# Interface_Connector.net
KiCad netlist of a schematic drawn in Altium Designer
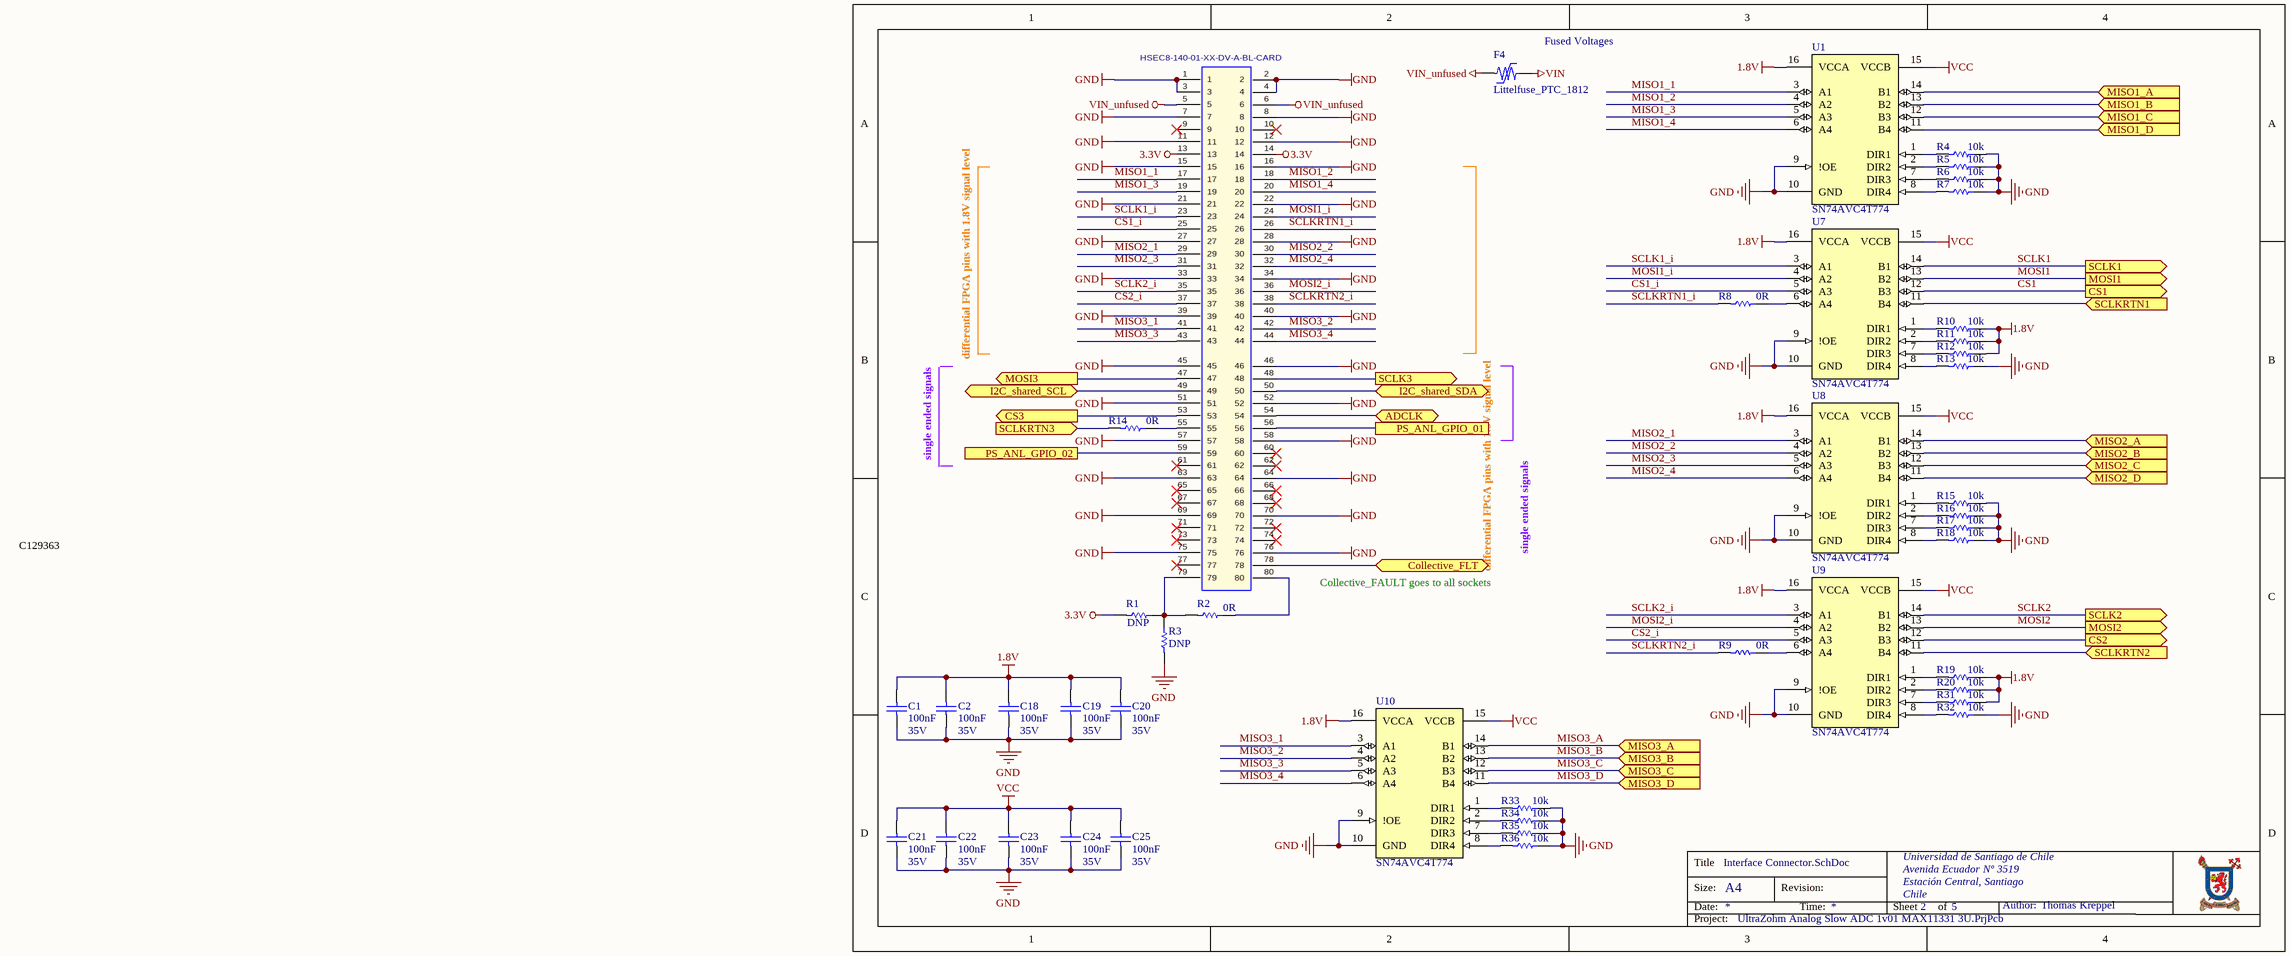
[diagram p0: Interface Connector.SchDoc]

(export (version "E")
  (design (tool "Eeschema 10.0.6"))
  (components
    (comp (ref "C1")
      (value "100nF")
      (footprint "CAP_0603")
      (description "Capacitor")
      (fields
        (field (name "MPN") "C0603C104M5RACTU")
        (field (name "MF") "KEMET")
        (field (name "VOLTAGE") "35V")
        (field (name "PUBLISHER") "Altium Limited")
      )
      (libsource (lib "Componentes_SOC") (part "Cap_0603"))
    )
    (comp (ref "C2")
      (value "100nF")
      (footprint "CAP_0603")
      (description "Capacitor")
      (fields
        (field (name "MPN") "C0603C104M5RACTU")
        (field (name "MF") "KEMET")
        (field (name "VOLTAGE") "35V")
        (field (name "PUBLISHER") "Altium Limited")
      )
      (libsource (lib "Componentes_SOC") (part "Cap_0603"))
    )
    (comp (ref "C18")
      (value "100nF")
      (footprint "CAP_0603")
      (description "Capacitor")
      (fields
        (field (name "MPN") "C0603C104M5RACTU")
        (field (name "MF") "KEMET")
        (field (name "VOLTAGE") "35V")
        (field (name "PUBLISHER") "Altium Limited")
      )
      (libsource (lib "Componentes_SOC") (part "Cap_0603"))
    )
    (comp (ref "C19")
      (value "100nF")
      (footprint "CAP_0603")
      (description "Capacitor")
      (fields
        (field (name "MPN") "C0603C104M5RACTU")
        (field (name "MF") "KEMET")
        (field (name "VOLTAGE") "35V")
        (field (name "PUBLISHER") "Altium Limited")
      )
      (libsource (lib "Componentes_SOC") (part "Cap_0603"))
    )
    (comp (ref "C20")
      (value "100nF")
      (footprint "CAP_0603")
      (description "Capacitor")
      (fields
        (field (name "MPN") "C0603C104M5RACTU")
        (field (name "MF") "KEMET")
        (field (name "VOLTAGE") "35V")
        (field (name "PUBLISHER") "Altium Limited")
      )
      (libsource (lib "Componentes_SOC") (part "Cap_0603"))
    )
    (comp (ref "C21")
      (value "100nF")
      (footprint "CAP_0603")
      (description "Capacitor")
      (fields
        (field (name "MPN") "C0603C104M5RACTU")
        (field (name "MF") "KEMET")
        (field (name "VOLTAGE") "35V")
        (field (name "PUBLISHER") "Altium Limited")
      )
      (libsource (lib "Componentes_SOC") (part "Cap_0603"))
    )
    (comp (ref "C22")
      (value "100nF")
      (footprint "CAP_0603")
      (description "Capacitor")
      (fields
        (field (name "MPN") "C0603C104M5RACTU")
        (field (name "MF") "KEMET")
        (field (name "VOLTAGE") "35V")
        (field (name "PUBLISHER") "Altium Limited")
      )
      (libsource (lib "Componentes_SOC") (part "Cap_0603"))
    )
    (comp (ref "C23")
      (value "100nF")
      (footprint "CAP_0603")
      (description "Capacitor")
      (fields
        (field (name "MPN") "C0603C104M5RACTU")
        (field (name "MF") "KEMET")
        (field (name "VOLTAGE") "35V")
        (field (name "PUBLISHER") "Altium Limited")
      )
      (libsource (lib "Componentes_SOC") (part "Cap_0603"))
    )
    (comp (ref "C24")
      (value "100nF")
      (footprint "CAP_0603")
      (description "Capacitor")
      (fields
        (field (name "MPN") "C0603C104M5RACTU")
        (field (name "MF") "KEMET")
        (field (name "VOLTAGE") "35V")
        (field (name "PUBLISHER") "Altium Limited")
      )
      (libsource (lib "Componentes_SOC") (part "Cap_0603"))
    )
    (comp (ref "C25")
      (value "100nF")
      (footprint "CAP_0603")
      (description "Capacitor")
      (fields
        (field (name "MPN") "C0603C104M5RACTU")
        (field (name "MF") "KEMET")
        (field (name "VOLTAGE") "35V")
        (field (name "PUBLISHER") "Altium Limited")
      )
      (libsource (lib "Componentes_SOC") (part "Cap_0603"))
    )
    (comp (ref "F4")
      (value "Littelfuse_PTC_1812")
      (footprint "1812_PTC_Polyfuse_Littelfuse")
      (description "POLYSWITCH RESETTABLE DEVICES")
      (fields
        (field (name "MPN") "miniASMDC110F/24")
        (field (name "MF") "Littelfuse")
        (field (name "CREATED") "2019_02_10_AGeiger")
        (field (name "CREATED FROM") "MHlatky")
      )
      (libsource (lib "user") (part "Littelfuse_PTC_1812"))
    )
    (comp (ref "R1")
      (value "DNP")
      (footprint "RES_0603")
      (fields
        (field (name "MPN") "CRCW06030000Z0EA")
        (field (name "TOLERANCE") "1%")
        (field (name "PUBLISHER") "Altium Limited")
      )
      (libsource (lib "Componentes_SOC") (part "Res0603"))
    )
    (comp (ref "R2")
      (value "0R")
      (footprint "RES_0603")
      (fields
        (field (name "MPN") "CRCW06030000Z0EA")
        (field (name "TOLERANCE") "1%")
        (field (name "PUBLISHER") "Altium Limited")
      )
      (libsource (lib "Componentes_SOC") (part "Res0603"))
    )
    (comp (ref "R3")
      (value "DNP")
      (footprint "RES_0603")
      (fields
        (field (name "MPN") "CRCW06030000Z0EA")
        (field (name "TOLERANCE") "1%")
        (field (name "PUBLISHER") "Altium Limited")
      )
      (libsource (lib "Componentes_SOC") (part "Res0603"))
    )
    (comp (ref "R4")
      (value "10k")
      (footprint "RES_0603")
      (fields (field (name "TOLERANCE") "1%") (field (name "PUBLISHER") "Altium Limited"))
      (libsource (lib "Componentes_SOC") (part "Res0603"))
    )
    (comp (ref "R5")
      (value "10k")
      (footprint "RES_0603")
      (fields (field (name "TOLERANCE") "1%") (field (name "PUBLISHER") "Altium Limited"))
      (libsource (lib "Componentes_SOC") (part "Res0603"))
    )
    (comp (ref "R6")
      (value "10k")
      (footprint "RES_0603")
      (fields (field (name "TOLERANCE") "1%") (field (name "PUBLISHER") "Altium Limited"))
      (libsource (lib "Componentes_SOC") (part "Res0603"))
    )
    (comp (ref "R7")
      (value "10k")
      (footprint "RES_0603")
      (fields (field (name "TOLERANCE") "1%") (field (name "PUBLISHER") "Altium Limited"))
      (libsource (lib "Componentes_SOC") (part "Res0603"))
    )
    (comp (ref "R8")
      (value "0R")
      (footprint "RES_0603")
      (fields (field (name "TOLERANCE") "1%") (field (name "PUBLISHER") "Altium Limited"))
      (libsource (lib "Componentes_SOC") (part "Res0603"))
    )
    (comp (ref "R9")
      (value "0R")
      (footprint "RES_0603")
      (fields (field (name "TOLERANCE") "1%") (field (name "PUBLISHER") "Altium Limited"))
      (libsource (lib "Componentes_SOC") (part "Res0603"))
    )
    (comp (ref "R10")
      (value "10k")
      (footprint "RES_0603")
      (fields (field (name "TOLERANCE") "1%") (field (name "PUBLISHER") "Altium Limited"))
      (libsource (lib "Componentes_SOC") (part "Res0603"))
    )
    (comp (ref "R11")
      (value "10k")
      (footprint "RES_0603")
      (fields (field (name "TOLERANCE") "1%") (field (name "PUBLISHER") "Altium Limited"))
      (libsource (lib "Componentes_SOC") (part "Res0603"))
    )
    (comp (ref "R12")
      (value "10k")
      (footprint "RES_0603")
      (fields (field (name "TOLERANCE") "1%") (field (name "PUBLISHER") "Altium Limited"))
      (libsource (lib "Componentes_SOC") (part "Res0603"))
    )
    (comp (ref "R13")
      (value "10k")
      (footprint "RES_0603")
      (fields (field (name "TOLERANCE") "1%") (field (name "PUBLISHER") "Altium Limited"))
      (libsource (lib "Componentes_SOC") (part "Res0603"))
    )
    (comp (ref "R14")
      (value "0R")
      (footprint "RES_0603")
      (fields (field (name "TOLERANCE") "1%") (field (name "PUBLISHER") "Altium Limited"))
      (libsource (lib "Componentes_SOC") (part "Res0603"))
    )
    (comp (ref "R15")
      (value "10k")
      (footprint "RES_0603")
      (fields (field (name "TOLERANCE") "1%") (field (name "PUBLISHER") "Altium Limited"))
      (libsource (lib "Componentes_SOC") (part "Res0603"))
    )
    (comp (ref "R16")
      (value "10k")
      (footprint "RES_0603")
      (fields (field (name "TOLERANCE") "1%") (field (name "PUBLISHER") "Altium Limited"))
      (libsource (lib "Componentes_SOC") (part "Res0603"))
    )
    (comp (ref "R17")
      (value "10k")
      (footprint "RES_0603")
      (fields (field (name "TOLERANCE") "1%") (field (name "PUBLISHER") "Altium Limited"))
      (libsource (lib "Componentes_SOC") (part "Res0603"))
    )
    (comp (ref "R18")
      (value "10k")
      (footprint "RES_0603")
      (fields (field (name "TOLERANCE") "1%") (field (name "PUBLISHER") "Altium Limited"))
      (libsource (lib "Componentes_SOC") (part "Res0603"))
    )
    (comp (ref "R19")
      (value "10k")
      (footprint "RES_0603")
      (fields (field (name "TOLERANCE") "1%") (field (name "PUBLISHER") "Altium Limited"))
      (libsource (lib "Componentes_SOC") (part "Res0603"))
    )
    (comp (ref "R20")
      (value "10k")
      (footprint "RES_0603")
      (fields (field (name "TOLERANCE") "1%") (field (name "PUBLISHER") "Altium Limited"))
      (libsource (lib "Componentes_SOC") (part "Res0603"))
    )
    (comp (ref "R31")
      (value "10k")
      (footprint "RES_0603")
      (fields (field (name "TOLERANCE") "1%") (field (name "PUBLISHER") "Altium Limited"))
      (libsource (lib "Componentes_SOC") (part "Res0603"))
    )
    (comp (ref "R32")
      (value "10k")
      (footprint "RES_0603")
      (fields (field (name "TOLERANCE") "1%") (field (name "PUBLISHER") "Altium Limited"))
      (libsource (lib "Componentes_SOC") (part "Res0603"))
    )
    (comp (ref "R33")
      (value "10k")
      (footprint "RES_0603")
      (fields (field (name "TOLERANCE") "1%") (field (name "PUBLISHER") "Altium Limited"))
      (libsource (lib "Componentes_SOC") (part "Res0603"))
    )
    (comp (ref "R34")
      (value "10k")
      (footprint "RES_0603")
      (fields (field (name "TOLERANCE") "1%") (field (name "PUBLISHER") "Altium Limited"))
      (libsource (lib "Componentes_SOC") (part "Res0603"))
    )
    (comp (ref "R35")
      (value "10k")
      (footprint "RES_0603")
      (fields (field (name "TOLERANCE") "1%") (field (name "PUBLISHER") "Altium Limited"))
      (libsource (lib "Componentes_SOC") (part "Res0603"))
    )
    (comp (ref "R36")
      (value "10k")
      (footprint "RES_0603")
      (fields (field (name "TOLERANCE") "1%") (field (name "PUBLISHER") "Altium Limited"))
      (libsource (lib "Componentes_SOC") (part "Res0603"))
    )
    (comp (ref "U1")
      (value "SN74AVC4T774")
      (footprint "TSOP65P640X120-16N")
      (fields
        (field (name "MF") "Texas Instruments")
        (field (name "MPN") "SN74AVC4T77PW")
        (field (name "LCSC PART NUMBER") "C129363")
        (field (name "CREATED") "2020_05_Kreppel")
      )
      (libsource (lib "Componentes_SOC") (part "SN74AVC4T774"))
    )
    (comp (ref "U7")
      (value "SN74AVC4T774")
      (footprint "TSOP65P640X120-16N")
      (fields
        (field (name "MF") "Texas Instruments")
        (field (name "MPN") "SN74AVC4T77PW")
        (field (name "LCSC PART NUMBER") "C129363")
        (field (name "CREATED") "2020_05_Kreppel")
      )
      (libsource (lib "Componentes_SOC") (part "SN74AVC4T774"))
    )
    (comp (ref "U8")
      (value "SN74AVC4T774")
      (footprint "TSOP65P640X120-16N")
      (fields
        (field (name "MF") "Texas Instruments")
        (field (name "MPN") "SN74AVC4T77PW")
        (field (name "LCSC PART NUMBER") "C129363")
        (field (name "CREATED") "2020_05_Kreppel")
      )
      (libsource (lib "Componentes_SOC") (part "SN74AVC4T774"))
    )
    (comp (ref "U9")
      (value "SN74AVC4T774")
      (footprint "TSOP65P640X120-16N")
      (fields
        (field (name "MF") "Texas Instruments")
        (field (name "MPN") "SN74AVC4T77PW")
        (field (name "LCSC PART NUMBER") "C129363")
        (field (name "CREATED") "2020_05_Kreppel")
      )
      (libsource (lib "Componentes_SOC") (part "SN74AVC4T774"))
    )
    (comp (ref "U10")
      (value "SN74AVC4T774")
      (footprint "TSOP65P640X120-16N")
      (fields
        (field (name "MF") "Texas Instruments")
        (field (name "MPN") "SN74AVC4T77PW")
        (field (name "LCSC PART NUMBER") "C129363")
        (field (name "CREATED") "2020_05_Kreppel")
      )
      (libsource (lib "Componentes_SOC") (part "SN74AVC4T774"))
    )
    (comp (ref "X1")
      (value "HSEC8-140-01-XX-DV-A-BL-CARD")
      (footprint "HSEC8-140-01-XX-DV-A-BL-CARD")
      (description "Mating Card Layout for HSEC8-140-01-XX-DV-A-BL")
      (fields (field (name "MF") "SAMTEC") (field (name "CREATED") "2018_04_23_AGeiger"))
      (libsource (lib "Samtec") (part "HSEC8-140-01-XX-DV-A-BL-CARD"))
    )
  )
  (nets
    (net (code "1") (name "/ADCLK") (class "Default")
      (node (ref "X1") (pin "54") (pinfunction "54_54") (pintype "passive"))
    )
    (net (code "2") (name "/CS1") (class "Default")
      (node (ref "U7") (pin "12") (pinfunction "B3_12") (pintype "bidirectional"))
    )
    (net (code "3") (name "/CS1_i") (class "Default")
      (node (ref "U7") (pin "5") (pinfunction "A3_5") (pintype "bidirectional"))
      (node (ref "X1") (pin "25") (pinfunction "25_25") (pintype "passive"))
    )
    (net (code "4") (name "/CS2") (class "Default")
      (node (ref "U9") (pin "12") (pinfunction "B3_12") (pintype "bidirectional"))
    )
    (net (code "5") (name "/CS2_i") (class "Default")
      (node (ref "U9") (pin "5") (pinfunction "A3_5") (pintype "bidirectional"))
      (node (ref "X1") (pin "37") (pinfunction "37_37") (pintype "passive"))
    )
    (net (code "6") (name "/CS3") (class "Default")
      (node (ref "X1") (pin "53") (pinfunction "53_53") (pintype "passive"))
    )
    (net (code "7") (name "/Collective_FLT") (class "Default")
      (node (ref "X1") (pin "78") (pinfunction "78_78") (pintype "passive"))
    )
    (net (code "8") (name "/I2C_shared_SCL") (class "Default")
      (node (ref "X1") (pin "49") (pinfunction "49_49") (pintype "passive"))
    )
    (net (code "9") (name "/I2C_shared_SDA") (class "Default")
      (node (ref "X1") (pin "50") (pinfunction "50_50") (pintype "passive"))
    )
    (net (code "10") (name "/MISO1_1") (class "Default")
      (node (ref "U1") (pin "3") (pinfunction "A1_3") (pintype "bidirectional"))
      (node (ref "X1") (pin "17") (pinfunction "17_17") (pintype "passive"))
    )
    (net (code "11") (name "/MISO1_2") (class "Default")
      (node (ref "U1") (pin "4") (pinfunction "A2_4") (pintype "bidirectional"))
      (node (ref "X1") (pin "18") (pinfunction "18_18") (pintype "passive"))
    )
    (net (code "12") (name "/MISO1_3") (class "Default")
      (node (ref "U1") (pin "5") (pinfunction "A3_5") (pintype "bidirectional"))
      (node (ref "X1") (pin "19") (pinfunction "19_19") (pintype "passive"))
    )
    (net (code "13") (name "/MISO1_4") (class "Default")
      (node (ref "U1") (pin "6") (pinfunction "A4_6") (pintype "bidirectional"))
      (node (ref "X1") (pin "20") (pinfunction "20_20") (pintype "passive"))
    )
    (net (code "14") (name "/MISO1_A") (class "Default")
      (node (ref "U1") (pin "14") (pinfunction "B1_14") (pintype "bidirectional"))
    )
    (net (code "15") (name "/MISO1_B") (class "Default")
      (node (ref "U1") (pin "13") (pinfunction "B2_13") (pintype "bidirectional"))
    )
    (net (code "16") (name "/MISO1_C") (class "Default")
      (node (ref "U1") (pin "12") (pinfunction "B3_12") (pintype "bidirectional"))
    )
    (net (code "17") (name "/MISO1_D") (class "Default")
      (node (ref "U1") (pin "11") (pinfunction "B4_11") (pintype "bidirectional"))
    )
    (net (code "18") (name "/MISO2_1") (class "Default")
      (node (ref "U8") (pin "3") (pinfunction "A1_3") (pintype "bidirectional"))
      (node (ref "X1") (pin "29") (pinfunction "29_29") (pintype "passive"))
    )
    (net (code "19") (name "/MISO2_2") (class "Default")
      (node (ref "U8") (pin "4") (pinfunction "A2_4") (pintype "bidirectional"))
      (node (ref "X1") (pin "30") (pinfunction "30_30") (pintype "passive"))
    )
    (net (code "20") (name "/MISO2_3") (class "Default")
      (node (ref "U8") (pin "5") (pinfunction "A3_5") (pintype "bidirectional"))
      (node (ref "X1") (pin "31") (pinfunction "31_31") (pintype "passive"))
    )
    (net (code "21") (name "/MISO2_4") (class "Default")
      (node (ref "U8") (pin "6") (pinfunction "A4_6") (pintype "bidirectional"))
      (node (ref "X1") (pin "32") (pinfunction "32_32") (pintype "passive"))
    )
    (net (code "22") (name "/MISO2_A") (class "Default")
      (node (ref "U8") (pin "14") (pinfunction "B1_14") (pintype "bidirectional"))
    )
    (net (code "23") (name "/MISO2_B") (class "Default")
      (node (ref "U8") (pin "13") (pinfunction "B2_13") (pintype "bidirectional"))
    )
    (net (code "24") (name "/MISO2_C") (class "Default")
      (node (ref "U8") (pin "12") (pinfunction "B3_12") (pintype "bidirectional"))
    )
    (net (code "25") (name "/MISO2_D") (class "Default")
      (node (ref "U8") (pin "11") (pinfunction "B4_11") (pintype "bidirectional"))
    )
    (net (code "26") (name "/MISO3_1") (class "Default")
      (node (ref "U10") (pin "3") (pinfunction "A1_3") (pintype "bidirectional"))
      (node (ref "X1") (pin "41") (pinfunction "41_41") (pintype "passive"))
    )
    (net (code "27") (name "/MISO3_2") (class "Default")
      (node (ref "U10") (pin "4") (pinfunction "A2_4") (pintype "bidirectional"))
      (node (ref "X1") (pin "42") (pinfunction "42_42") (pintype "passive"))
    )
    (net (code "28") (name "/MISO3_3") (class "Default")
      (node (ref "U10") (pin "5") (pinfunction "A3_5") (pintype "bidirectional"))
      (node (ref "X1") (pin "43") (pinfunction "43_43") (pintype "passive"))
    )
    (net (code "29") (name "/MISO3_4") (class "Default")
      (node (ref "U10") (pin "6") (pinfunction "A4_6") (pintype "bidirectional"))
      (node (ref "X1") (pin "44") (pinfunction "44_44") (pintype "passive"))
    )
    (net (code "30") (name "/MISO3_A") (class "Default")
      (node (ref "U10") (pin "14") (pinfunction "B1_14") (pintype "bidirectional"))
    )
    (net (code "31") (name "/MISO3_B") (class "Default")
      (node (ref "U10") (pin "13") (pinfunction "B2_13") (pintype "bidirectional"))
    )
    (net (code "32") (name "/MISO3_C") (class "Default")
      (node (ref "U10") (pin "12") (pinfunction "B3_12") (pintype "bidirectional"))
    )
    (net (code "33") (name "/MISO3_D") (class "Default")
      (node (ref "U10") (pin "11") (pinfunction "B4_11") (pintype "bidirectional"))
    )
    (net (code "34") (name "/MOSI1") (class "Default")
      (node (ref "U7") (pin "13") (pinfunction "B2_13") (pintype "bidirectional"))
    )
    (net (code "35") (name "/MOSI1_i") (class "Default")
      (node (ref "U7") (pin "4") (pinfunction "A2_4") (pintype "bidirectional"))
      (node (ref "X1") (pin "24") (pinfunction "24_24") (pintype "passive"))
    )
    (net (code "36") (name "/MOSI2") (class "Default")
      (node (ref "U9") (pin "13") (pinfunction "B2_13") (pintype "bidirectional"))
    )
    (net (code "37") (name "/MOSI2_i") (class "Default")
      (node (ref "U9") (pin "4") (pinfunction "A2_4") (pintype "bidirectional"))
      (node (ref "X1") (pin "36") (pinfunction "36_36") (pintype "passive"))
    )
    (net (code "38") (name "/MOSI3") (class "Default")
      (node (ref "X1") (pin "47") (pinfunction "47_47") (pintype "passive"))
    )
    (net (code "39") (name "/PS_ANL_GPIO_01") (class "Default")
      (node (ref "X1") (pin "56") (pinfunction "56_56") (pintype "passive"))
    )
    (net (code "40") (name "/PS_ANL_GPIO_02") (class "Default")
      (node (ref "X1") (pin "59") (pinfunction "59_59") (pintype "passive"))
    )
    (net (code "41") (name "/SCLK1") (class "Default")
      (node (ref "U7") (pin "14") (pinfunction "B1_14") (pintype "bidirectional"))
    )
    (net (code "42") (name "/SCLK1_i") (class "Default")
      (node (ref "U7") (pin "3") (pinfunction "A1_3") (pintype "bidirectional"))
      (node (ref "X1") (pin "23") (pinfunction "23_23") (pintype "passive"))
    )
    (net (code "43") (name "/SCLK2") (class "Default")
      (node (ref "U9") (pin "14") (pinfunction "B1_14") (pintype "bidirectional"))
    )
    (net (code "44") (name "/SCLK2_i") (class "Default")
      (node (ref "U9") (pin "3") (pinfunction "A1_3") (pintype "bidirectional"))
      (node (ref "X1") (pin "35") (pinfunction "35_35") (pintype "passive"))
    )
    (net (code "45") (name "/SCLK3") (class "Default")
      (node (ref "X1") (pin "48") (pinfunction "48_48") (pintype "passive"))
    )
    (net (code "46") (name "/SCLKRTN1") (class "Default")
      (node (ref "U7") (pin "11") (pinfunction "B4_11") (pintype "bidirectional"))
    )
    (net (code "47") (name "/SCLKRTN1_i") (class "Default")
      (node (ref "R8") (pin "2") (pinfunction "2_2") (pintype "passive"))
      (node (ref "X1") (pin "26") (pinfunction "26_26") (pintype "passive"))
    )
    (net (code "48") (name "/SCLKRTN2") (class "Default")
      (node (ref "U9") (pin "11") (pinfunction "B4_11") (pintype "bidirectional"))
    )
    (net (code "49") (name "/SCLKRTN2_i") (class "Default")
      (node (ref "R9") (pin "2") (pinfunction "2_2") (pintype "passive"))
      (node (ref "X1") (pin "38") (pinfunction "38_38") (pintype "passive"))
    )
    (net (code "50") (name "/SCLKRTN3") (class "Default")
      (node (ref "R14") (pin "2") (pinfunction "2_2") (pintype "passive"))
    )
    (net (code "51") (name "1.8V") (class "Default")
      (node (ref "C1") (pin "1") (pinfunction "1_1") (pintype "passive"))
      (node (ref "C18") (pin "1") (pinfunction "1_1") (pintype "passive"))
      (node (ref "C19") (pin "1") (pinfunction "1_1") (pintype "passive"))
      (node (ref "C2") (pin "1") (pinfunction "1_1") (pintype "passive"))
      (node (ref "C20") (pin "1") (pinfunction "1_1") (pintype "passive"))
      (node (ref "R10") (pin "1") (pinfunction "1_1") (pintype "passive"))
      (node (ref "R11") (pin "1") (pinfunction "1_1") (pintype "passive"))
      (node (ref "R12") (pin "1") (pinfunction "1_1") (pintype "passive"))
      (node (ref "R19") (pin "1") (pinfunction "1_1") (pintype "passive"))
      (node (ref "R20") (pin "1") (pinfunction "1_1") (pintype "passive"))
      (node (ref "R31") (pin "1") (pinfunction "1_1") (pintype "passive"))
      (node (ref "U1") (pin "16") (pinfunction "VCCA_16") (pintype "power_in"))
      (node (ref "U10") (pin "16") (pinfunction "VCCA_16") (pintype "power_in"))
      (node (ref "U7") (pin "16") (pinfunction "VCCA_16") (pintype "power_in"))
      (node (ref "U8") (pin "16") (pinfunction "VCCA_16") (pintype "power_in"))
      (node (ref "U9") (pin "16") (pinfunction "VCCA_16") (pintype "power_in"))
    )
    (net (code "52") (name "3.3V") (class "Default")
      (node (ref "R1") (pin "2") (pinfunction "2_2") (pintype "passive"))
      (node (ref "X1") (pin "13") (pinfunction "13_13") (pintype "passive"))
      (node (ref "X1") (pin "14") (pinfunction "14_14") (pintype "passive"))
    )
    (net (code "53") (name "GND") (class "Default")
      (node (ref "C1") (pin "2") (pinfunction "2_2") (pintype "passive"))
      (node (ref "C18") (pin "2") (pinfunction "2_2") (pintype "passive"))
      (node (ref "C19") (pin "2") (pinfunction "2_2") (pintype "passive"))
      (node (ref "C2") (pin "2") (pinfunction "2_2") (pintype "passive"))
      (node (ref "C20") (pin "2") (pinfunction "2_2") (pintype "passive"))
      (node (ref "C21") (pin "2") (pinfunction "2_2") (pintype "passive"))
      (node (ref "C22") (pin "2") (pinfunction "2_2") (pintype "passive"))
      (node (ref "C23") (pin "2") (pinfunction "2_2") (pintype "passive"))
      (node (ref "C24") (pin "2") (pinfunction "2_2") (pintype "passive"))
      (node (ref "C25") (pin "2") (pinfunction "2_2") (pintype "passive"))
      (node (ref "R13") (pin "1") (pinfunction "1_1") (pintype "passive"))
      (node (ref "R15") (pin "1") (pinfunction "1_1") (pintype "passive"))
      (node (ref "R16") (pin "1") (pinfunction "1_1") (pintype "passive"))
      (node (ref "R17") (pin "1") (pinfunction "1_1") (pintype "passive"))
      (node (ref "R18") (pin "1") (pinfunction "1_1") (pintype "passive"))
      (node (ref "R3") (pin "2") (pinfunction "2_2") (pintype "passive"))
      (node (ref "R32") (pin "1") (pinfunction "1_1") (pintype "passive"))
      (node (ref "R33") (pin "1") (pinfunction "1_1") (pintype "passive"))
      (node (ref "R34") (pin "1") (pinfunction "1_1") (pintype "passive"))
      (node (ref "R35") (pin "1") (pinfunction "1_1") (pintype "passive"))
      (node (ref "R36") (pin "1") (pinfunction "1_1") (pintype "passive"))
      (node (ref "R4") (pin "1") (pinfunction "1_1") (pintype "passive"))
      (node (ref "R5") (pin "1") (pinfunction "1_1") (pintype "passive"))
      (node (ref "R6") (pin "1") (pinfunction "1_1") (pintype "passive"))
      (node (ref "R7") (pin "1") (pinfunction "1_1") (pintype "passive"))
      (node (ref "U1") (pin "10") (pinfunction "GND_10") (pintype "power_in"))
      (node (ref "U1") (pin "9") (pinfunction "!OE_9") (pintype "input"))
      (node (ref "U10") (pin "10") (pinfunction "GND_10") (pintype "power_in"))
      (node (ref "U10") (pin "9") (pinfunction "!OE_9") (pintype "input"))
      (node (ref "U7") (pin "10") (pinfunction "GND_10") (pintype "power_in"))
      (node (ref "U7") (pin "9") (pinfunction "!OE_9") (pintype "input"))
      (node (ref "U8") (pin "10") (pinfunction "GND_10") (pintype "power_in"))
      (node (ref "U8") (pin "9") (pinfunction "!OE_9") (pintype "input"))
      (node (ref "U9") (pin "10") (pinfunction "GND_10") (pintype "power_in"))
      (node (ref "U9") (pin "9") (pinfunction "!OE_9") (pintype "input"))
      (node (ref "X1") (pin "1") (pinfunction "1_1") (pintype "passive"))
      (node (ref "X1") (pin "11") (pinfunction "11_11") (pintype "passive"))
      (node (ref "X1") (pin "12") (pinfunction "12_12") (pintype "passive"))
      (node (ref "X1") (pin "15") (pinfunction "15_15") (pintype "passive"))
      (node (ref "X1") (pin "16") (pinfunction "16_16") (pintype "passive"))
      (node (ref "X1") (pin "2") (pinfunction "2_2") (pintype "passive"))
      (node (ref "X1") (pin "21") (pinfunction "21_21") (pintype "passive"))
      (node (ref "X1") (pin "22") (pinfunction "22_22") (pintype "passive"))
      (node (ref "X1") (pin "27") (pinfunction "27_27") (pintype "passive"))
      (node (ref "X1") (pin "28") (pinfunction "28_28") (pintype "passive"))
      (node (ref "X1") (pin "3") (pinfunction "3_3") (pintype "passive"))
      (node (ref "X1") (pin "33") (pinfunction "33_33") (pintype "passive"))
      (node (ref "X1") (pin "34") (pinfunction "34_34") (pintype "passive"))
      (node (ref "X1") (pin "39") (pinfunction "39_39") (pintype "passive"))
      (node (ref "X1") (pin "4") (pinfunction "4_4") (pintype "passive"))
      (node (ref "X1") (pin "40") (pinfunction "40_40") (pintype "passive"))
      (node (ref "X1") (pin "45") (pinfunction "45_45") (pintype "passive"))
      (node (ref "X1") (pin "46") (pinfunction "46_46") (pintype "passive"))
      (node (ref "X1") (pin "51") (pinfunction "51_51") (pintype "passive"))
      (node (ref "X1") (pin "52") (pinfunction "52_52") (pintype "passive"))
      (node (ref "X1") (pin "57") (pinfunction "57_57") (pintype "passive"))
      (node (ref "X1") (pin "58") (pinfunction "58_58") (pintype "passive"))
      (node (ref "X1") (pin "63") (pinfunction "63_63") (pintype "passive"))
      (node (ref "X1") (pin "64") (pinfunction "64_64") (pintype "passive"))
      (node (ref "X1") (pin "69") (pinfunction "69_69") (pintype "passive"))
      (node (ref "X1") (pin "7") (pinfunction "7_7") (pintype "passive"))
      (node (ref "X1") (pin "70") (pinfunction "70_70") (pintype "passive"))
      (node (ref "X1") (pin "75") (pinfunction "75_75") (pintype "passive"))
      (node (ref "X1") (pin "76") (pinfunction "76_76") (pintype "passive"))
      (node (ref "X1") (pin "8") (pinfunction "8_8") (pintype "passive"))
    )
    (net (code "54") (name "Net-(R1-Pad1)") (class "Default")
      (node (ref "R1") (pin "1") (pinfunction "1_1") (pintype "passive"))
      (node (ref "R2") (pin "2") (pinfunction "2_2") (pintype "passive"))
      (node (ref "R3") (pin "1") (pinfunction "1_1") (pintype "passive"))
      (node (ref "X1") (pin "79") (pinfunction "79_79") (pintype "passive"))
    )
    (net (code "55") (name "Net-(R2-Pad1)") (class "Default")
      (node (ref "R2") (pin "1") (pinfunction "1_1") (pintype "passive"))
      (node (ref "X1") (pin "80") (pinfunction "80_80") (pintype "passive"))
    )
    (net (code "56") (name "Net-(R14-Pad1)") (class "Default")
      (node (ref "R14") (pin "1") (pinfunction "1_1") (pintype "passive"))
      (node (ref "X1") (pin "55") (pinfunction "55_55") (pintype "passive"))
    )
    (net (code "57") (name "Net-(U1-DIR1)") (class "Default")
      (node (ref "R4") (pin "2") (pinfunction "2_2") (pintype "passive"))
      (node (ref "U1") (pin "1") (pinfunction "DIR1_1") (pintype "input"))
    )
    (net (code "58") (name "Net-(U1-DIR2)") (class "Default")
      (node (ref "R5") (pin "2") (pinfunction "2_2") (pintype "passive"))
      (node (ref "U1") (pin "2") (pinfunction "DIR2_2") (pintype "input"))
    )
    (net (code "59") (name "Net-(U1-DIR3)") (class "Default")
      (node (ref "R6") (pin "2") (pinfunction "2_2") (pintype "passive"))
      (node (ref "U1") (pin "7") (pinfunction "DIR3_7") (pintype "input"))
    )
    (net (code "60") (name "Net-(U1-DIR4)") (class "Default")
      (node (ref "R7") (pin "2") (pinfunction "2_2") (pintype "passive"))
      (node (ref "U1") (pin "8") (pinfunction "DIR4_8") (pintype "input"))
    )
    (net (code "61") (name "Net-(U7-A4)") (class "Default")
      (node (ref "R8") (pin "1") (pinfunction "1_1") (pintype "passive"))
      (node (ref "U7") (pin "6") (pinfunction "A4_6") (pintype "bidirectional"))
    )
    (net (code "62") (name "Net-(U7-DIR1)") (class "Default")
      (node (ref "R10") (pin "2") (pinfunction "2_2") (pintype "passive"))
      (node (ref "U7") (pin "1") (pinfunction "DIR1_1") (pintype "input"))
    )
    (net (code "63") (name "Net-(U7-DIR2)") (class "Default")
      (node (ref "R11") (pin "2") (pinfunction "2_2") (pintype "passive"))
      (node (ref "U7") (pin "2") (pinfunction "DIR2_2") (pintype "input"))
    )
    (net (code "64") (name "Net-(U7-DIR3)") (class "Default")
      (node (ref "R12") (pin "2") (pinfunction "2_2") (pintype "passive"))
      (node (ref "U7") (pin "7") (pinfunction "DIR3_7") (pintype "input"))
    )
    (net (code "65") (name "Net-(U7-DIR4)") (class "Default")
      (node (ref "R13") (pin "2") (pinfunction "2_2") (pintype "passive"))
      (node (ref "U7") (pin "8") (pinfunction "DIR4_8") (pintype "input"))
    )
    (net (code "66") (name "Net-(U8-DIR1)") (class "Default")
      (node (ref "R15") (pin "2") (pinfunction "2_2") (pintype "passive"))
      (node (ref "U8") (pin "1") (pinfunction "DIR1_1") (pintype "input"))
    )
    (net (code "67") (name "Net-(U8-DIR2)") (class "Default")
      (node (ref "R16") (pin "2") (pinfunction "2_2") (pintype "passive"))
      (node (ref "U8") (pin "2") (pinfunction "DIR2_2") (pintype "input"))
    )
    (net (code "68") (name "Net-(U8-DIR3)") (class "Default")
      (node (ref "R17") (pin "2") (pinfunction "2_2") (pintype "passive"))
      (node (ref "U8") (pin "7") (pinfunction "DIR3_7") (pintype "input"))
    )
    (net (code "69") (name "Net-(U8-DIR4)") (class "Default")
      (node (ref "R18") (pin "2") (pinfunction "2_2") (pintype "passive"))
      (node (ref "U8") (pin "8") (pinfunction "DIR4_8") (pintype "input"))
    )
    (net (code "70") (name "Net-(U9-A4)") (class "Default")
      (node (ref "R9") (pin "1") (pinfunction "1_1") (pintype "passive"))
      (node (ref "U9") (pin "6") (pinfunction "A4_6") (pintype "bidirectional"))
    )
    (net (code "71") (name "Net-(U9-DIR1)") (class "Default")
      (node (ref "R19") (pin "2") (pinfunction "2_2") (pintype "passive"))
      (node (ref "U9") (pin "1") (pinfunction "DIR1_1") (pintype "input"))
    )
    (net (code "72") (name "Net-(U9-DIR2)") (class "Default")
      (node (ref "R20") (pin "2") (pinfunction "2_2") (pintype "passive"))
      (node (ref "U9") (pin "2") (pinfunction "DIR2_2") (pintype "input"))
    )
    (net (code "73") (name "Net-(U9-DIR3)") (class "Default")
      (node (ref "R31") (pin "2") (pinfunction "2_2") (pintype "passive"))
      (node (ref "U9") (pin "7") (pinfunction "DIR3_7") (pintype "input"))
    )
    (net (code "74") (name "Net-(U9-DIR4)") (class "Default")
      (node (ref "R32") (pin "2") (pinfunction "2_2") (pintype "passive"))
      (node (ref "U9") (pin "8") (pinfunction "DIR4_8") (pintype "input"))
    )
    (net (code "75") (name "Net-(U10-DIR1)") (class "Default")
      (node (ref "R33") (pin "2") (pinfunction "2_2") (pintype "passive"))
      (node (ref "U10") (pin "1") (pinfunction "DIR1_1") (pintype "input"))
    )
    (net (code "76") (name "Net-(U10-DIR2)") (class "Default")
      (node (ref "R34") (pin "2") (pinfunction "2_2") (pintype "passive"))
      (node (ref "U10") (pin "2") (pinfunction "DIR2_2") (pintype "input"))
    )
    (net (code "77") (name "Net-(U10-DIR3)") (class "Default")
      (node (ref "R35") (pin "2") (pinfunction "2_2") (pintype "passive"))
      (node (ref "U10") (pin "7") (pinfunction "DIR3_7") (pintype "input"))
    )
    (net (code "78") (name "Net-(U10-DIR4)") (class "Default")
      (node (ref "R36") (pin "2") (pinfunction "2_2") (pintype "passive"))
      (node (ref "U10") (pin "8") (pinfunction "DIR4_8") (pintype "input"))
    )
    (net (code "79") (name "VCC") (class "Default")
      (node (ref "C21") (pin "1") (pinfunction "1_1") (pintype "passive"))
      (node (ref "C22") (pin "1") (pinfunction "1_1") (pintype "passive"))
      (node (ref "C23") (pin "1") (pinfunction "1_1") (pintype "passive"))
      (node (ref "C24") (pin "1") (pinfunction "1_1") (pintype "passive"))
      (node (ref "C25") (pin "1") (pinfunction "1_1") (pintype "passive"))
      (node (ref "U1") (pin "15") (pinfunction "VCCB_15") (pintype "power_in"))
      (node (ref "U10") (pin "15") (pinfunction "VCCB_15") (pintype "power_in"))
      (node (ref "U7") (pin "15") (pinfunction "VCCB_15") (pintype "power_in"))
      (node (ref "U8") (pin "15") (pinfunction "VCCB_15") (pintype "power_in"))
      (node (ref "U9") (pin "15") (pinfunction "VCCB_15") (pintype "power_in"))
    )
    (net (code "80") (name "VIN") (class "Default")
      (node (ref "F4") (pin "2") (pinfunction "2_2") (pintype "passive"))
    )
    (net (code "81") (name "VIN_unfused") (class "Default")
      (node (ref "F4") (pin "1") (pinfunction "1_1") (pintype "passive"))
      (node (ref "X1") (pin "5") (pinfunction "5_5") (pintype "passive"))
      (node (ref "X1") (pin "6") (pinfunction "6_6") (pintype "passive"))
    )
    (net (code "82") (name "unconnected-(X1-Pad9)") (class "Default")
      (node (ref "X1") (pin "9") (pinfunction "9_9") (pintype "passive+no_connect"))
    )
    (net (code "83") (name "unconnected-(X1-Pad10)") (class "Default")
      (node (ref "X1") (pin "10") (pinfunction "10_10") (pintype "passive+no_connect"))
    )
    (net (code "84") (name "unconnected-(X1-Pad60)") (class "Default")
      (node (ref "X1") (pin "60") (pinfunction "60_60") (pintype "passive+no_connect"))
    )
    (net (code "85") (name "unconnected-(X1-Pad61)") (class "Default")
      (node (ref "X1") (pin "61") (pinfunction "61_61") (pintype "passive+no_connect"))
    )
    (net (code "86") (name "unconnected-(X1-Pad62)") (class "Default")
      (node (ref "X1") (pin "62") (pinfunction "62_62") (pintype "passive+no_connect"))
    )
    (net (code "87") (name "unconnected-(X1-Pad65)") (class "Default")
      (node (ref "X1") (pin "65") (pinfunction "65_65") (pintype "passive+no_connect"))
    )
    (net (code "88") (name "unconnected-(X1-Pad66)") (class "Default")
      (node (ref "X1") (pin "66") (pinfunction "66_66") (pintype "passive+no_connect"))
    )
    (net (code "89") (name "unconnected-(X1-Pad67)") (class "Default")
      (node (ref "X1") (pin "67") (pinfunction "67_67") (pintype "passive+no_connect"))
    )
    (net (code "90") (name "unconnected-(X1-Pad68)") (class "Default")
      (node (ref "X1") (pin "68") (pinfunction "68_68") (pintype "passive+no_connect"))
    )
    (net (code "91") (name "unconnected-(X1-Pad71)") (class "Default")
      (node (ref "X1") (pin "71") (pinfunction "71_71") (pintype "passive+no_connect"))
    )
    (net (code "92") (name "unconnected-(X1-Pad72)") (class "Default")
      (node (ref "X1") (pin "72") (pinfunction "72_72") (pintype "passive+no_connect"))
    )
    (net (code "93") (name "unconnected-(X1-Pad73)") (class "Default")
      (node (ref "X1") (pin "73") (pinfunction "73_73") (pintype "passive+no_connect"))
    )
    (net (code "94") (name "unconnected-(X1-Pad74)") (class "Default")
      (node (ref "X1") (pin "74") (pinfunction "74_74") (pintype "passive+no_connect"))
    )
    (net (code "95") (name "unconnected-(X1-Pad77)") (class "Default")
      (node (ref "X1") (pin "77") (pinfunction "77_77") (pintype "passive+no_connect"))
    )
  )
)
